# Sheet1.net
KiCad netlist of a schematic drawn in Altium Designer
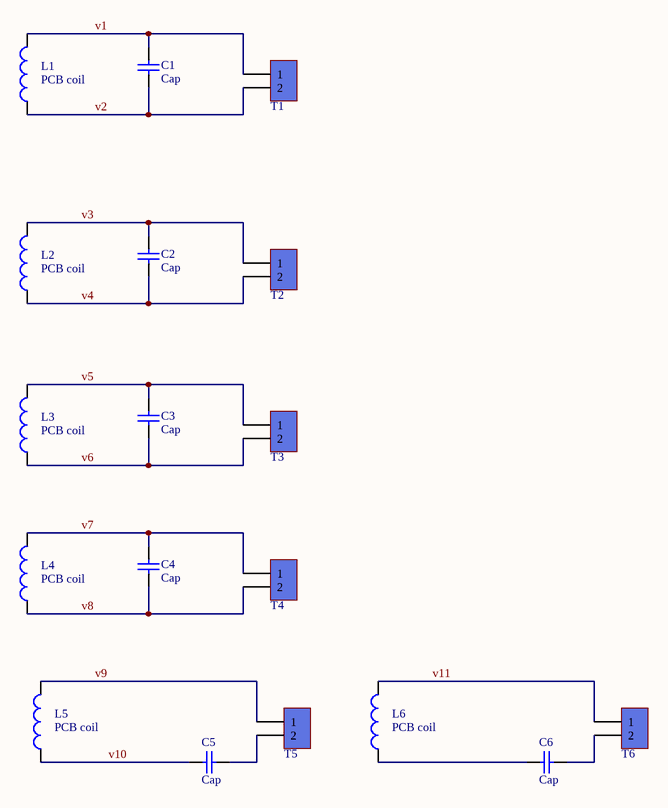
[diagram p0: Sheet1.SchDoc]

(export (version "E")
  (design (tool "Eeschema 10.0.6"))
  (components
    (comp (ref "C1")
      (value "Cap")
      (footprint "CAP_MKT")
      (description "Capacitor")
      (fields (field (name "PUBLISHER") "Altium Limited"))
      (libsource (lib "Miscellaneous Devices") (part "Cap"))
    )
    (comp (ref "C2")
      (value "Cap")
      (footprint "CAP_MKT")
      (description "Capacitor")
      (fields (field (name "PUBLISHER") "Altium Limited"))
      (libsource (lib "Miscellaneous Devices") (part "Cap"))
    )
    (comp (ref "C3")
      (value "Cap")
      (footprint "CAP_MKT")
      (description "Capacitor")
      (fields (field (name "PUBLISHER") "Altium Limited"))
      (libsource (lib "Miscellaneous Devices") (part "Cap"))
    )
    (comp (ref "C4")
      (value "Cap")
      (footprint "CAP_MKT")
      (description "Capacitor")
      (fields (field (name "PUBLISHER") "Altium Limited"))
      (libsource (lib "Miscellaneous Devices") (part "Cap"))
    )
    (comp (ref "C5")
      (value "Cap")
      (footprint "CAP_MKT")
      (description "Capacitor")
      (fields (field (name "PUBLISHER") "Altium Limited"))
      (libsource (lib "Miscellaneous Devices") (part "Cap"))
    )
    (comp (ref "C6")
      (value "Cap")
      (footprint "CAP_MKT")
      (description "Capacitor")
      (fields (field (name "PUBLISHER") "Altium Limited"))
      (libsource (lib "Miscellaneous Devices") (part "Cap"))
    )
    (comp (ref "L1")
      (value "PCB coil")
      (footprint "coil_30*30_1mm_2layer")
      (fields (field (name "PUBLISHER") "Altium Limited"))
      (libsource (lib "Miscellaneous Devices") (part "Inductor"))
    )
    (comp (ref "L2")
      (value "PCB coil")
      (footprint "coil_30*30_2mm_1layer")
      (fields (field (name "PUBLISHER") "Altium Limited"))
      (libsource (lib "Miscellaneous Devices") (part "Inductor"))
    )
    (comp (ref "L3")
      (value "PCB coil")
      (footprint "coil_30*30_2mm_2layer")
      (fields (field (name "PUBLISHER") "Altium Limited"))
      (libsource (lib "Miscellaneous Devices") (part "Inductor"))
    )
    (comp (ref "L4")
      (value "PCB coil")
      (footprint "coil_30*30_3mm_2layer")
      (fields (field (name "PUBLISHER") "Altium Limited"))
      (libsource (lib "Miscellaneous Devices") (part "Inductor"))
    )
    (comp (ref "L5")
      (value "PCB coil")
      (footprint "COIL_HEX_50*50_2layer")
      (fields (field (name "PUBLISHER") "Altium Limited"))
      (libsource (lib "Miscellaneous Devices") (part "Inductor"))
    )
    (comp (ref "L6")
      (value "PCB coil")
      (footprint "COIL_HEX_50*50_2LAYER_2mm")
      (fields (field (name "PUBLISHER") "Altium Limited"))
      (libsource (lib "Miscellaneous Devices") (part "Inductor"))
    )
    (comp (ref "T1")
      (value "Terminal")
      (footprint "Terminal 1*2_coil")
      (description "Terminal 2 Pin 250VAC 16A")
      (fields (field (name "DESIGNER") "Seyed Mohsen Ghasemain") (field (name "E-MAIL") "picpars@gmail.com"))
      (libsource (lib "PicPars.com_usefully_Library") (part "Terminal 1*2"))
    )
    (comp (ref "T2")
      (value "Terminal")
      (footprint "Terminal 1*2_coil")
      (description "Terminal 2 Pin 250VAC 16A")
      (fields (field (name "DESIGNER") "Seyed Mohsen Ghasemain") (field (name "E-MAIL") "picpars@gmail.com"))
      (libsource (lib "PicPars.com_usefully_Library") (part "Terminal 1*2"))
    )
    (comp (ref "T3")
      (value "Terminal")
      (footprint "Terminal 1*2_coil")
      (description "Terminal 2 Pin 250VAC 16A")
      (fields (field (name "DESIGNER") "Seyed Mohsen Ghasemain") (field (name "E-MAIL") "picpars@gmail.com"))
      (libsource (lib "PicPars.com_usefully_Library") (part "Terminal 1*2"))
    )
    (comp (ref "T4")
      (value "Terminal")
      (footprint "Terminal 1*2_coil")
      (description "Terminal 2 Pin 250VAC 16A")
      (fields (field (name "DESIGNER") "Seyed Mohsen Ghasemain") (field (name "E-MAIL") "picpars@gmail.com"))
      (libsource (lib "PicPars.com_usefully_Library") (part "Terminal 1*2"))
    )
    (comp (ref "T5")
      (value "Terminal")
      (footprint "Terminal 1*2_coil")
      (description "Terminal 2 Pin 250VAC 16A")
      (fields (field (name "DESIGNER") "Seyed Mohsen Ghasemain") (field (name "E-MAIL") "picpars@gmail.com"))
      (libsource (lib "PicPars.com_usefully_Library") (part "Terminal 1*2"))
    )
    (comp (ref "T6")
      (value "Terminal")
      (footprint "Terminal 1*2_coil")
      (description "Terminal 2 Pin 250VAC 16A")
      (fields (field (name "DESIGNER") "Seyed Mohsen Ghasemain") (field (name "E-MAIL") "picpars@gmail.com"))
      (libsource (lib "PicPars.com_usefully_Library") (part "Terminal 1*2"))
    )
  )
  (nets
    (net (code "1") (name "/v1") (class "Default")
      (node (ref "C1") (pin "2") (pinfunction "2_2") (pintype "passive"))
      (node (ref "L1") (pin "2") (pinfunction "2_2") (pintype "passive"))
      (node (ref "T1") (pin "1") (pinfunction "1_1") (pintype "passive"))
    )
    (net (code "2") (name "/v2") (class "Default")
      (node (ref "C1") (pin "1") (pinfunction "1_1") (pintype "passive"))
      (node (ref "L1") (pin "1") (pinfunction "1_1") (pintype "passive"))
      (node (ref "T1") (pin "2") (pinfunction "2_2") (pintype "passive"))
    )
    (net (code "3") (name "/v3") (class "Default")
      (node (ref "C2") (pin "2") (pinfunction "2_2") (pintype "passive"))
      (node (ref "L2") (pin "2") (pinfunction "2_2") (pintype "passive"))
      (node (ref "T2") (pin "1") (pinfunction "1_1") (pintype "passive"))
    )
    (net (code "4") (name "/v4") (class "Default")
      (node (ref "C2") (pin "1") (pinfunction "1_1") (pintype "passive"))
      (node (ref "L2") (pin "1") (pinfunction "1_1") (pintype "passive"))
      (node (ref "T2") (pin "2") (pinfunction "2_2") (pintype "passive"))
    )
    (net (code "5") (name "/v5") (class "Default")
      (node (ref "C3") (pin "2") (pinfunction "2_2") (pintype "passive"))
      (node (ref "L3") (pin "2") (pinfunction "2_2") (pintype "passive"))
      (node (ref "T3") (pin "1") (pinfunction "1_1") (pintype "passive"))
    )
    (net (code "6") (name "/v6") (class "Default")
      (node (ref "C3") (pin "1") (pinfunction "1_1") (pintype "passive"))
      (node (ref "L3") (pin "1") (pinfunction "1_1") (pintype "passive"))
      (node (ref "T3") (pin "2") (pinfunction "2_2") (pintype "passive"))
    )
    (net (code "7") (name "/v7") (class "Default")
      (node (ref "C4") (pin "2") (pinfunction "2_2") (pintype "passive"))
      (node (ref "L4") (pin "2") (pinfunction "2_2") (pintype "passive"))
      (node (ref "T4") (pin "1") (pinfunction "1_1") (pintype "passive"))
    )
    (net (code "8") (name "/v8") (class "Default")
      (node (ref "C4") (pin "1") (pinfunction "1_1") (pintype "passive"))
      (node (ref "L4") (pin "1") (pinfunction "1_1") (pintype "passive"))
      (node (ref "T4") (pin "2") (pinfunction "2_2") (pintype "passive"))
    )
    (net (code "9") (name "/v9") (class "Default")
      (node (ref "L5") (pin "2") (pinfunction "2_2") (pintype "passive"))
      (node (ref "T5") (pin "1") (pinfunction "1_1") (pintype "passive"))
    )
    (net (code "10") (name "/v10") (class "Default")
      (node (ref "C5") (pin "2") (pinfunction "2_2") (pintype "passive"))
      (node (ref "L5") (pin "1") (pinfunction "1_1") (pintype "passive"))
    )
    (net (code "11") (name "/v11") (class "Default")
      (node (ref "L6") (pin "2") (pinfunction "2_2") (pintype "passive"))
      (node (ref "T6") (pin "1") (pinfunction "1_1") (pintype "passive"))
    )
    (net (code "12") (name "Net-(C5-Pad1)") (class "Default")
      (node (ref "C5") (pin "1") (pinfunction "1_1") (pintype "passive"))
      (node (ref "T5") (pin "2") (pinfunction "2_2") (pintype "passive"))
    )
    (net (code "13") (name "Net-(C6-Pad1)") (class "Default")
      (node (ref "C6") (pin "1") (pinfunction "1_1") (pintype "passive"))
      (node (ref "T6") (pin "2") (pinfunction "2_2") (pintype "passive"))
    )
    (net (code "14") (name "Net-(C6-Pad2)") (class "Default")
      (node (ref "C6") (pin "2") (pinfunction "2_2") (pintype "passive"))
      (node (ref "L6") (pin "1") (pinfunction "1_1") (pintype "passive"))
    )
  )
)
